# Electronic_Cricket.net
KiCad netlist of a schematic drawn in EAGLE
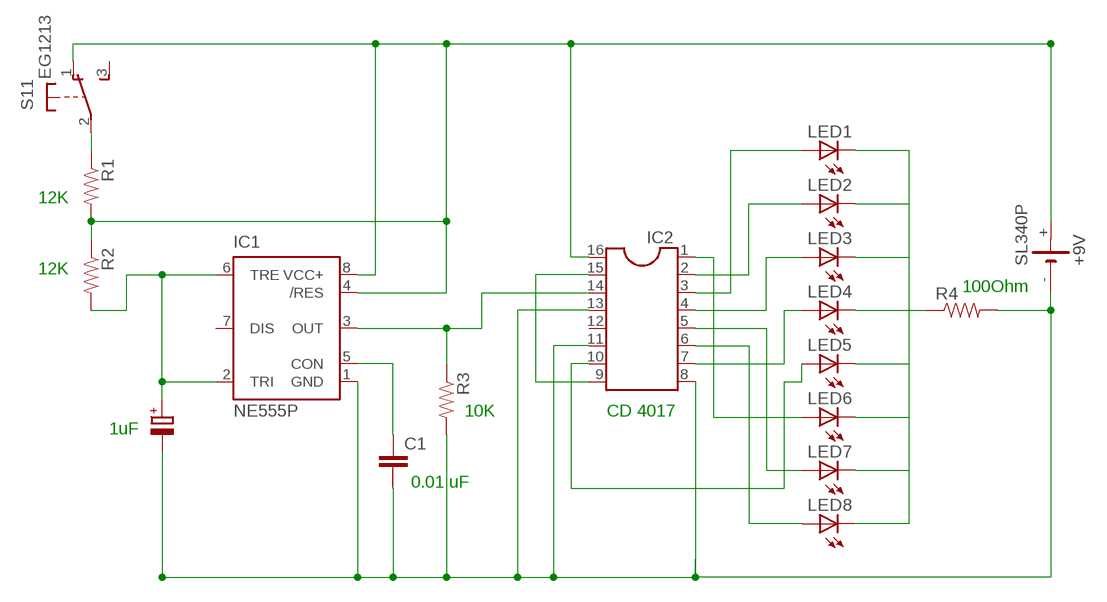
[diagram p0: schematic, sheet 1]

(export (version "E")
  (design (tool "Eeschema 10.0.6"))
  (components
    (comp (ref "+9V")
      (value "SL340P")
      (footprint "eagle-import:SL-340_P3.6V")
      (libsource (lib "eagle-import") (part "SL340P"))
    )
    (comp (ref "C1")
      (value "C2.5/6")
      (footprint "eagle-import:C2.5-6")
      (libsource (lib "eagle-import") (part "C2.5/6"))
    )
    (comp (ref "IC1")
      (value "NE555P")
      (footprint "eagle-import:DIL-08")
      (fields (field (name "MF") "Arrow Electronics") (field (name "MPN") "NE555N"))
      (libsource (lib "eagle-import") (part "NE555P"))
    )
    (comp (ref "IC2")
      (value "DIL16")
      (footprint "eagle-import:DIL16")
      (libsource (lib "eagle-import") (part "DIL16"))
    )
    (comp (ref "LED1")
      (value "LEDB156")
      (footprint "eagle-import:Q62902-B156")
      (libsource (lib "eagle-import") (part "LEDB156"))
    )
    (comp (ref "LED2")
      (value "LEDB156")
      (footprint "eagle-import:Q62902-B156")
      (libsource (lib "eagle-import") (part "LEDB156"))
    )
    (comp (ref "LED3")
      (value "LEDB156")
      (footprint "eagle-import:Q62902-B156")
      (libsource (lib "eagle-import") (part "LEDB156"))
    )
    (comp (ref "LED4")
      (value "LEDB156")
      (footprint "eagle-import:Q62902-B156")
      (libsource (lib "eagle-import") (part "LEDB156"))
    )
    (comp (ref "LED5")
      (value "LEDB156")
      (footprint "eagle-import:Q62902-B156")
      (libsource (lib "eagle-import") (part "LEDB156"))
    )
    (comp (ref "LED6")
      (value "LEDB156")
      (footprint "eagle-import:Q62902-B156")
      (libsource (lib "eagle-import") (part "LEDB156"))
    )
    (comp (ref "LED7")
      (value "LEDB156")
      (footprint "eagle-import:Q62902-B156")
      (libsource (lib "eagle-import") (part "LEDB156"))
    )
    (comp (ref "LED8")
      (value "LEDB156")
      (footprint "eagle-import:Q62902-B156")
      (libsource (lib "eagle-import") (part "LEDB156"))
    )
    (comp (ref "R1")
      (value "RESISTORAXIAL-0.3")
      (footprint "eagle-import:AXIAL-0.3")
      (libsource (lib "eagle-import") (part "RESISTORAXIAL-0.3"))
    )
    (comp (ref "R2")
      (value "RESISTORAXIAL-0.3")
      (footprint "eagle-import:AXIAL-0.3")
      (libsource (lib "eagle-import") (part "RESISTORAXIAL-0.3"))
    )
    (comp (ref "R3")
      (value "RESISTORAXIAL-0.3")
      (footprint "eagle-import:AXIAL-0.3")
      (libsource (lib "eagle-import") (part "RESISTORAXIAL-0.3"))
    )
    (comp (ref "R4")
      (value "RESISTORAXIAL-0.3")
      (footprint "eagle-import:AXIAL-0.3")
      (libsource (lib "eagle-import") (part "RESISTORAXIAL-0.3"))
    )
    (comp (ref "S1")
      (value "EG1213")
      (footprint "eagle-import:EG1213")
      (libsource (lib "eagle-import") (part "EG1213"))
    )
  )
  (nets
    (net (code "1") (name "Net-(IC1-CON)") (class "Default")
      (node (ref "C1") (pin "1") (pinfunction "1_1") (pintype "passive"))
      (node (ref "IC1") (pin "5") (pinfunction "CON_5") (pintype "input"))
    )
    (net (code "2") (name "Net-(IC1-GND)") (class "Default")
      (node (ref "+9V") (pin "-") (pinfunction "-_-") (pintype "passive"))
      (node (ref "C1") (pin "2") (pinfunction "2_2") (pintype "passive"))
      (node (ref "IC1") (pin "1") (pinfunction "GND_1") (pintype "power_in"))
      (node (ref "IC2") (pin "11") (pinfunction "11_11") (pintype "passive"))
      (node (ref "IC2") (pin "13") (pinfunction "13_13") (pintype "passive"))
      (node (ref "IC2") (pin "8") (pinfunction "8_8") (pintype "passive"))
      (node (ref "R3") (pin "P$2") (pinfunction "2_P$2") (pintype "passive"))
      (node (ref "R4") (pin "P$2") (pinfunction "2_P$2") (pintype "passive"))
    )
    (net (code "3") (name "Net-(IC1-OUT)") (class "Default")
      (node (ref "IC1") (pin "3") (pinfunction "OUT_3") (pintype "output"))
      (node (ref "IC2") (pin "14") (pinfunction "14_14") (pintype "passive"))
      (node (ref "R3") (pin "P$1") (pinfunction "1_P$1") (pintype "passive"))
    )
    (net (code "4") (name "Net-(IC1-TRE)") (class "Default")
      (node (ref "IC1") (pin "2") (pinfunction "TRI_2") (pintype "input"))
      (node (ref "IC1") (pin "6") (pinfunction "TRE_6") (pintype "input"))
      (node (ref "R2") (pin "P$2") (pinfunction "2_P$2") (pintype "passive"))
    )
    (net (code "5") (name "Net-(IC1-VCC+)") (class "Default")
      (node (ref "+9V") (pin "+") (pinfunction "+_+") (pintype "passive"))
      (node (ref "IC1") (pin "4") (pinfunction "/RES_4") (pintype "input"))
      (node (ref "IC1") (pin "8") (pinfunction "VCC+_8") (pintype "power_in"))
      (node (ref "IC2") (pin "16") (pinfunction "16_16") (pintype "passive"))
      (node (ref "R1") (pin "P$2") (pinfunction "2_P$2") (pintype "passive"))
      (node (ref "R2") (pin "P$1") (pinfunction "1_P$1") (pintype "passive"))
      (node (ref "S1") (pin "1") (pinfunction "O_1") (pintype "passive"))
    )
    (net (code "6") (name "Net-(IC2-Pad1)") (class "Default")
      (node (ref "IC2") (pin "1") (pinfunction "1_1") (pintype "passive"))
      (node (ref "LED6") (pin "A") (pinfunction "A_A") (pintype "passive"))
    )
    (net (code "7") (name "Net-(IC2-Pad2)") (class "Default")
      (node (ref "IC2") (pin "2") (pinfunction "2_2") (pintype "passive"))
      (node (ref "LED2") (pin "A") (pinfunction "A_A") (pintype "passive"))
    )
    (net (code "8") (name "Net-(IC2-Pad3)") (class "Default")
      (node (ref "IC2") (pin "3") (pinfunction "3_3") (pintype "passive"))
      (node (ref "LED1") (pin "A") (pinfunction "A_A") (pintype "passive"))
    )
    (net (code "9") (name "Net-(IC2-Pad4)") (class "Default")
      (node (ref "IC2") (pin "4") (pinfunction "4_4") (pintype "passive"))
      (node (ref "LED3") (pin "A") (pinfunction "A_A") (pintype "passive"))
    )
    (net (code "10") (name "Net-(IC2-Pad5)") (class "Default")
      (node (ref "IC2") (pin "5") (pinfunction "5_5") (pintype "passive"))
      (node (ref "LED7") (pin "A") (pinfunction "A_A") (pintype "passive"))
    )
    (net (code "11") (name "Net-(IC2-Pad6)") (class "Default")
      (node (ref "IC2") (pin "6") (pinfunction "6_6") (pintype "passive"))
      (node (ref "LED8") (pin "A") (pinfunction "A_A") (pintype "passive"))
    )
    (net (code "12") (name "Net-(IC2-Pad7)") (class "Default")
      (node (ref "IC2") (pin "7") (pinfunction "7_7") (pintype "passive"))
      (node (ref "LED4") (pin "A") (pinfunction "A_A") (pintype "passive"))
    )
    (net (code "13") (name "Net-(IC2-Pad10)") (class "Default")
      (node (ref "IC2") (pin "10") (pinfunction "10_10") (pintype "passive"))
      (node (ref "LED5") (pin "A") (pinfunction "A_A") (pintype "passive"))
    )
    (net (code "14") (name "Net-(IC2-Pad15)") (class "Default")
      (node (ref "IC2") (pin "15") (pinfunction "15_15") (pintype "passive"))
      (node (ref "IC2") (pin "9") (pinfunction "9_9") (pintype "passive"))
    )
    (net (code "15") (name "Net-(LED1-C)") (class "Default")
      (node (ref "LED1") (pin "K") (pinfunction "C_K") (pintype "passive"))
      (node (ref "LED2") (pin "K") (pinfunction "C_K") (pintype "passive"))
      (node (ref "LED3") (pin "K") (pinfunction "C_K") (pintype "passive"))
      (node (ref "LED4") (pin "K") (pinfunction "C_K") (pintype "passive"))
      (node (ref "LED5") (pin "K") (pinfunction "C_K") (pintype "passive"))
      (node (ref "LED6") (pin "K") (pinfunction "C_K") (pintype "passive"))
      (node (ref "LED7") (pin "K") (pinfunction "C_K") (pintype "passive"))
      (node (ref "LED8") (pin "K") (pinfunction "C_K") (pintype "passive"))
      (node (ref "R4") (pin "P$1") (pinfunction "1_P$1") (pintype "passive"))
    )
    (net (code "16") (name "Net-(R1-1)") (class "Default")
      (node (ref "R1") (pin "P$1") (pinfunction "1_P$1") (pintype "passive"))
      (node (ref "S1") (pin "2") (pinfunction "P_2") (pintype "passive"))
    )
    (net (code "17") (name "unconnected-(IC1-DIS-Pad7)") (class "Default")
      (node (ref "IC1") (pin "7") (pinfunction "DIS_7") (pintype "input"))
    )
    (net (code "18") (name "unconnected-(IC2-Pad12)") (class "Default")
      (node (ref "IC2") (pin "12") (pinfunction "12_12") (pintype "passive"))
    )
    (net (code "19") (name "unconnected-(S1A-S-Pad3)") (class "Default")
      (node (ref "S1") (pin "3") (pinfunction "S_3") (pintype "passive"))
    )
  )
)
